# VibeBrain2.net
KiCad netlist of a schematic drawn in EAGLE
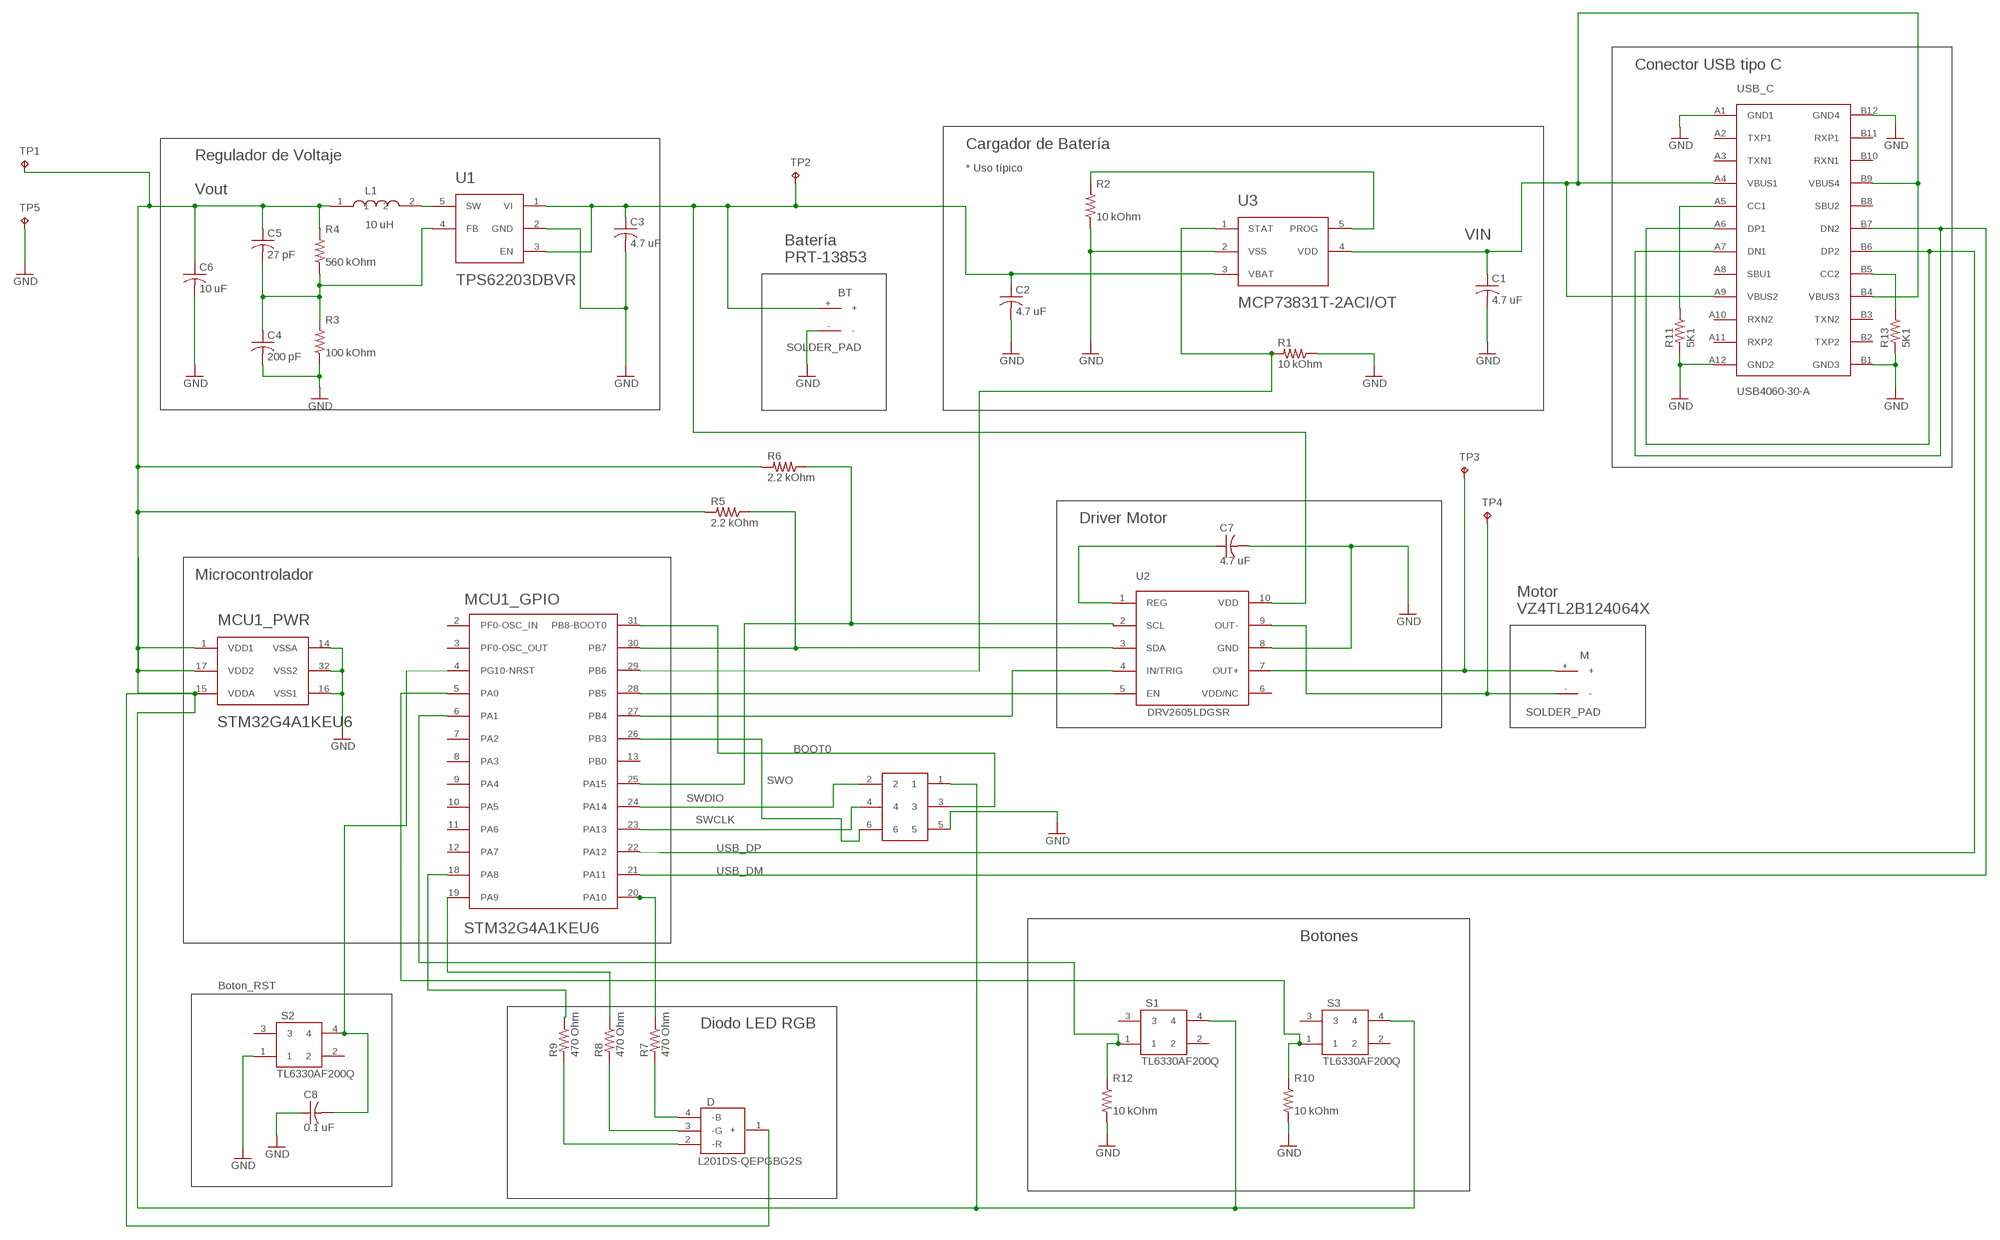
[diagram p0: schematic, sheet 1]

(export (version "E")
  (design (tool "Eeschema 10.0.6"))
  (components
    (comp (ref "BT")
      (value "SOLDER_PAD")
      (footprint "eagle-import:SMD")
      (libsource (lib "eagle-import") (part "PADS"))
    )
    (comp (ref "C1")
      (value "4.7 uF")
      (footprint "eagle-import:C0402")
      (fields (field (name "PARTNO") "GRM155R60J475ME47J"))
      (libsource (lib "eagle-import") (part "C-USC0402"))
    )
    (comp (ref "C2")
      (value "4.7 uF")
      (footprint "eagle-import:C0402")
      (fields (field (name "PARTNO") "GRM155R60J475ME47J"))
      (libsource (lib "eagle-import") (part "C-USC0402"))
    )
    (comp (ref "C3")
      (value "4.7 uF")
      (footprint "eagle-import:C0402")
      (fields (field (name "PARTNO") "GRM155R60J475ME47J"))
      (libsource (lib "eagle-import") (part "C-USC0402"))
    )
    (comp (ref "C4")
      (value "200 pF")
      (footprint "eagle-import:C0402")
      (fields (field (name "PARTNO") "GCM1555C1H201FA16D"))
      (libsource (lib "eagle-import") (part "C-USC0402"))
    )
    (comp (ref "C5")
      (value "27 pF")
      (footprint "eagle-import:C0402")
      (fields (field (name "PARTNO") "GCM1555C1H270JA16D"))
      (libsource (lib "eagle-import") (part "C-USC0402"))
    )
    (comp (ref "C6")
      (value "10 uF")
      (footprint "eagle-import:C0402")
      (fields (field (name "PARTNO") "GRM155R60J106ME05J"))
      (libsource (lib "eagle-import") (part "C-USC0402"))
    )
    (comp (ref "C7")
      (value "4.7 uF")
      (footprint "eagle-import:C0402")
      (fields (field (name "PARTNO") "GRM155R60J475ME47J"))
      (libsource (lib "eagle-import") (part "C-USC0402"))
    )
    (comp (ref "C8")
      (value "0.1 uF")
      (footprint "eagle-import:C0402")
      (fields (field (name "PARTNO") "GCM155R71C104KA55J"))
      (libsource (lib "eagle-import") (part "C-USC0402"))
    )
    (comp (ref "D")
      (value "L201DS-QEPGBG2S")
      (footprint "eagle-import:SMD")
      (libsource (lib "eagle-import") (part "L201DS-QEPGBG2S"))
    )
    (comp (ref "J1")
      (value "TC2030-IDC")
      (footprint "eagle-import:TC2030-IDC-FP")
      (libsource (lib "eagle-import") (part "TC2030-IDC-FP"))
    )
    (comp (ref "L1")
      (value "10 uH")
      (footprint "eagle-import:SMD")
      (fields (field (name "PARTNO") "LQW15DN100M00D"))
      (libsource (lib "eagle-import") (part "LQW15DN100M00D-ME"))
    )
    (comp (ref "M")
      (value "SOLDER_PAD")
      (footprint "eagle-import:SMD")
      (libsource (lib "eagle-import") (part "PADS"))
    )
    (comp (ref "MCU1")
      (value "STM32G4A1KEU6")
      (footprint "eagle-import:32-UFQFPN(5X5)")
      (fields (field (name "PARTNO") "STM32G4A1KEU6 "))
      (libsource (lib "eagle-import") (part "STM32G4A1KEU6"))
    )
    (comp (ref "R1")
      (value "10 kOhm")
      (footprint "eagle-import:R0402")
      (fields (field (name "PARTNO") "RMCF0402FT10K0"))
      (libsource (lib "eagle-import") (part "R-US_R0402"))
    )
    (comp (ref "R2")
      (value "10 kOhm")
      (footprint "eagle-import:R0402")
      (fields (field (name "PARTNO") "RMCF0402FT10K0"))
      (libsource (lib "eagle-import") (part "R-US_R0402"))
    )
    (comp (ref "R3")
      (value "100 kOhm")
      (footprint "eagle-import:R0402")
      (fields (field (name "PARTNO") "RMCF0402FT100K"))
      (libsource (lib "eagle-import") (part "R-US_R0402"))
    )
    (comp (ref "R4")
      (value "560 kOhm")
      (footprint "eagle-import:R0402")
      (fields (field (name "PARTNO") "ERJ-2RKF5603X"))
      (libsource (lib "eagle-import") (part "R-US_R0402"))
    )
    (comp (ref "R5")
      (value "2.2 kOhm")
      (footprint "eagle-import:R0402")
      (fields (field (name "PARTNO") "RMCF0402JT2K20"))
      (libsource (lib "eagle-import") (part "R-US_R0402"))
    )
    (comp (ref "R6")
      (value "2.2 kOhm")
      (footprint "eagle-import:R0402")
      (fields (field (name "PARTNO") "RMCF0402JT2K20"))
      (libsource (lib "eagle-import") (part "R-US_R0402"))
    )
    (comp (ref "R7")
      (value "470 Ohm")
      (footprint "eagle-import:R0402")
      (fields (field (name "PARTNO") "RMCF0402FT470R"))
      (libsource (lib "eagle-import") (part "R-US_R0402"))
    )
    (comp (ref "R8")
      (value "470 Ohm")
      (footprint "eagle-import:R0402")
      (fields (field (name "PARTNO") "RMCF0402FT470R"))
      (libsource (lib "eagle-import") (part "R-US_R0402"))
    )
    (comp (ref "R9")
      (value "470 Ohm")
      (footprint "eagle-import:R0402")
      (fields (field (name "PARTNO") "RMCF0402FT470R"))
      (libsource (lib "eagle-import") (part "R-US_R0402"))
    )
    (comp (ref "R10")
      (value "10 kOhm")
      (footprint "eagle-import:R0402")
      (fields (field (name "PARTNO") "RMCF0402FT10K0"))
      (libsource (lib "eagle-import") (part "R-US_R0402"))
    )
    (comp (ref "R11")
      (value "5K1")
      (footprint "eagle-import:R0402")
      (fields (field (name "PARTNO") "RC0402FR-075K1L"))
      (libsource (lib "eagle-import") (part "R-US_R0402"))
    )
    (comp (ref "R12")
      (value "10 kOhm")
      (footprint "eagle-import:R0402")
      (fields (field (name "PARTNO") "RMCF0402FT10K0"))
      (libsource (lib "eagle-import") (part "R-US_R0402"))
    )
    (comp (ref "R13")
      (value "5K1")
      (footprint "eagle-import:R0402")
      (fields (field (name "PARTNO") "RC0402FR-075K1L"))
      (libsource (lib "eagle-import") (part "R-US_R0402"))
    )
    (comp (ref "S1")
      (value "TL6330AF200Q")
      (footprint "eagle-import:SWITCH")
      (libsource (lib "eagle-import") (part "TL6330AF200Q"))
    )
    (comp (ref "S2")
      (value "TL6330AF200Q")
      (footprint "eagle-import:SWITCH")
      (libsource (lib "eagle-import") (part "TL6330AF200Q"))
    )
    (comp (ref "S3")
      (value "TL6330AF200Q")
      (footprint "eagle-import:SWITCH")
      (libsource (lib "eagle-import") (part "TL6330AF200Q"))
    )
    (comp (ref "TP1")
      (value "TPTP07SQ")
      (footprint "eagle-import:TP07SQ")
      (libsource (lib "eagle-import") (part "TPTP07SQ"))
    )
    (comp (ref "TP2")
      (value "TPTP07SQ")
      (footprint "eagle-import:TP07SQ")
      (libsource (lib "eagle-import") (part "TPTP07SQ"))
    )
    (comp (ref "TP3")
      (value "TPTP07SQ")
      (footprint "eagle-import:TP07SQ")
      (libsource (lib "eagle-import") (part "TPTP07SQ"))
    )
    (comp (ref "TP4")
      (value "TPTP07SQ")
      (footprint "eagle-import:TP07SQ")
      (libsource (lib "eagle-import") (part "TPTP07SQ"))
    )
    (comp (ref "TP5")
      (value "TPTP07SQ")
      (footprint "eagle-import:TP07SQ")
      (libsource (lib "eagle-import") (part "TPTP07SQ"))
    )
    (comp (ref "U1")
      (value "TPS62203DBVR")
      (footprint "eagle-import:SOT-23-5")
      (libsource (lib "eagle-import") (part "TPS62203DBVR"))
    )
    (comp (ref "U2")
      (value "DRV2605LDGSR")
      (footprint "eagle-import:10-VSSOP")
      (libsource (lib "eagle-import") (part "DRV2605LDGSR"))
    )
    (comp (ref "U3")
      (value "MCP73831T-2ACI/OT")
      (footprint "eagle-import:SOT-23-5")
      (libsource (lib "eagle-import") (part "MCP73831T-2ACI-OT"))
    )
    (comp (ref "USB_C")
      (value "USB4060-30-A")
      (footprint "eagle-import:USB_C")
      (libsource (lib "eagle-import") (part "USB4060-30-A"))
    )
  )
  (nets
    (net (code "1") (name "/VDD{slash}NC") (class "Default")
      (node (ref "U2") (pin "6") (pinfunction "VDD/NC_6") (pintype "power_in"))
    )
    (net (code "2") (name "GND") (class "Default")
      (node (ref "BT") (pin "-") (pinfunction "-_-") (pintype "passive"))
      (node (ref "C1") (pin "2") (pinfunction "2_2") (pintype "passive"))
      (node (ref "C2") (pin "2") (pinfunction "2_2") (pintype "passive"))
      (node (ref "C3") (pin "2") (pinfunction "2_2") (pintype "passive"))
      (node (ref "C4") (pin "2") (pinfunction "2_2") (pintype "passive"))
      (node (ref "C6") (pin "2") (pinfunction "2_2") (pintype "passive"))
      (node (ref "C7") (pin "2") (pinfunction "2_2") (pintype "passive"))
      (node (ref "C8") (pin "1") (pinfunction "1_1") (pintype "passive"))
      (node (ref "J1") (pin "5") (pinfunction "5_5") (pintype "passive"))
      (node (ref "MCU1") (pin "14") (pinfunction "VSSA_14") (pintype "passive"))
      (node (ref "MCU1") (pin "16") (pinfunction "VSS1_16") (pintype "passive"))
      (node (ref "MCU1") (pin "32") (pinfunction "VSS2_32") (pintype "passive"))
      (node (ref "R1") (pin "1") (pinfunction "1_1") (pintype "passive"))
      (node (ref "R10") (pin "2") (pinfunction "2_2") (pintype "passive"))
      (node (ref "R11") (pin "2") (pinfunction "2_2") (pintype "passive"))
      (node (ref "R12") (pin "2") (pinfunction "2_2") (pintype "passive"))
      (node (ref "R13") (pin "2") (pinfunction "2_2") (pintype "passive"))
      (node (ref "R2") (pin "1") (pinfunction "1_1") (pintype "passive"))
      (node (ref "R3") (pin "1") (pinfunction "1_1") (pintype "passive"))
      (node (ref "S2") (pin "1") (pinfunction "1_1") (pintype "passive"))
      (node (ref "TP5") (pin "TP") (pinfunction "TP_TP") (pintype "input"))
      (node (ref "U1") (pin "2") (pinfunction "GND_2") (pintype "passive"))
      (node (ref "U2") (pin "8") (pinfunction "GND_8") (pintype "passive"))
      (node (ref "U3") (pin "2") (pinfunction "VSS_2") (pintype "passive"))
      (node (ref "USB_C") (pin "A1") (pinfunction "GND1_A1") (pintype "power_in"))
      (node (ref "USB_C") (pin "A12") (pinfunction "GND2_A12") (pintype "power_in"))
      (node (ref "USB_C") (pin "B1") (pinfunction "GND3_B1") (pintype "power_in"))
      (node (ref "USB_C") (pin "B12") (pinfunction "GND4_B12") (pintype "power_in"))
    )
    (net (code "3") (name "Net-(D-+)") (class "Default")
      (node (ref "C5") (pin "1") (pinfunction "1_1") (pintype "passive"))
      (node (ref "C6") (pin "1") (pinfunction "1_1") (pintype "passive"))
      (node (ref "D") (pin "1") (pinfunction "+_1") (pintype "passive"))
      (node (ref "J1") (pin "1") (pinfunction "1_1") (pintype "passive"))
      (node (ref "L1") (pin "1") (pinfunction "1_1") (pintype "passive"))
      (node (ref "MCU1") (pin "1") (pinfunction "VDD1_1") (pintype "passive"))
      (node (ref "MCU1") (pin "15") (pinfunction "VDDA_15") (pintype "passive"))
      (node (ref "MCU1") (pin "17") (pinfunction "VDD2_17") (pintype "passive"))
      (node (ref "R4") (pin "2") (pinfunction "2_2") (pintype "passive"))
      (node (ref "R5") (pin "2") (pinfunction "2_2") (pintype "passive"))
      (node (ref "R6") (pin "2") (pinfunction "2_2") (pintype "passive"))
      (node (ref "S1") (pin "4") (pinfunction "4_4") (pintype "passive"))
      (node (ref "S3") (pin "4") (pinfunction "4_4") (pintype "passive"))
      (node (ref "TP1") (pin "TP") (pinfunction "TP_TP") (pintype "input"))
    )
    (net (code "4") (name "Net-(D--B)") (class "Default")
      (node (ref "D") (pin "4") (pinfunction "-B_4") (pintype "passive"))
      (node (ref "R7") (pin "2") (pinfunction "2_2") (pintype "passive"))
    )
    (net (code "5") (name "Net-(D--G)") (class "Default")
      (node (ref "D") (pin "3") (pinfunction "-G_3") (pintype "passive"))
      (node (ref "R8") (pin "2") (pinfunction "2_2") (pintype "passive"))
    )
    (net (code "6") (name "Net-(D--R)") (class "Default")
      (node (ref "D") (pin "2") (pinfunction "-R_2") (pintype "passive"))
      (node (ref "R9") (pin "2") (pinfunction "2_2") (pintype "passive"))
    )
    (net (code "7") (name "Net-(MCU1A-PA0)") (class "Default")
      (node (ref "MCU1") (pin "5") (pinfunction "PA0_5") (pintype "bidirectional"))
      (node (ref "R10") (pin "1") (pinfunction "1_1") (pintype "passive"))
      (node (ref "S3") (pin "1") (pinfunction "1_1") (pintype "passive"))
    )
    (net (code "8") (name "Net-(MCU1A-PA1)") (class "Default")
      (node (ref "MCU1") (pin "6") (pinfunction "PA1_6") (pintype "bidirectional"))
      (node (ref "R12") (pin "1") (pinfunction "1_1") (pintype "passive"))
      (node (ref "S1") (pin "1") (pinfunction "1_1") (pintype "passive"))
    )
    (net (code "9") (name "Net-(MCU1A-PA8)") (class "Default")
      (node (ref "MCU1") (pin "18") (pinfunction "PA8_18") (pintype "bidirectional"))
      (node (ref "R9") (pin "1") (pinfunction "1_1") (pintype "passive"))
    )
    (net (code "10") (name "Net-(MCU1A-PA9)") (class "Default")
      (node (ref "MCU1") (pin "19") (pinfunction "PA9_19") (pintype "bidirectional"))
      (node (ref "R8") (pin "1") (pinfunction "1_1") (pintype "passive"))
    )
    (net (code "11") (name "Net-(MCU1A-PA10)") (class "Default")
      (node (ref "MCU1") (pin "20") (pinfunction "PA10_20") (pintype "bidirectional"))
      (node (ref "R7") (pin "1") (pinfunction "1_1") (pintype "passive"))
    )
    (net (code "12") (name "Net-(MCU1A-PA11)") (class "Default")
      (node (ref "MCU1") (pin "21") (pinfunction "PA11_21") (pintype "bidirectional"))
      (node (ref "USB_C") (pin "A7") (pinfunction "DN1_A7") (pintype "bidirectional"))
      (node (ref "USB_C") (pin "B7") (pinfunction "DN2_B7") (pintype "bidirectional"))
    )
    (net (code "13") (name "Net-(MCU1A-PA12)") (class "Default")
      (node (ref "MCU1") (pin "22") (pinfunction "PA12_22") (pintype "bidirectional"))
      (node (ref "USB_C") (pin "A6") (pinfunction "DP1_A6") (pintype "bidirectional"))
      (node (ref "USB_C") (pin "B6") (pinfunction "DP2_B6") (pintype "bidirectional"))
    )
    (net (code "14") (name "Net-(MCU1A-PA13)") (class "Default")
      (node (ref "J1") (pin "4") (pinfunction "4_4") (pintype "passive"))
      (node (ref "MCU1") (pin "23") (pinfunction "PA13_23") (pintype "bidirectional"))
    )
    (net (code "15") (name "Net-(MCU1A-PA14)") (class "Default")
      (node (ref "J1") (pin "2") (pinfunction "2_2") (pintype "passive"))
      (node (ref "MCU1") (pin "24") (pinfunction "PA14_24") (pintype "bidirectional"))
    )
    (net (code "16") (name "Net-(MCU1A-PA15)") (class "Default")
      (node (ref "MCU1") (pin "25") (pinfunction "PA15_25") (pintype "bidirectional"))
      (node (ref "R6") (pin "1") (pinfunction "1_1") (pintype "passive"))
      (node (ref "U2") (pin "2") (pinfunction "SCL_2") (pintype "input"))
    )
    (net (code "17") (name "Net-(MCU1A-PB3)") (class "Default")
      (node (ref "J1") (pin "6") (pinfunction "6_6") (pintype "passive"))
      (node (ref "MCU1") (pin "26") (pinfunction "PB3_26") (pintype "bidirectional"))
    )
    (net (code "18") (name "Net-(MCU1A-PB4)") (class "Default")
      (node (ref "MCU1") (pin "27") (pinfunction "PB4_27") (pintype "bidirectional"))
      (node (ref "U2") (pin "4") (pinfunction "IN/TRIG_4") (pintype "input"))
    )
    (net (code "19") (name "Net-(MCU1A-PB5)") (class "Default")
      (node (ref "MCU1") (pin "28") (pinfunction "PB5_28") (pintype "bidirectional"))
      (node (ref "U2") (pin "5") (pinfunction "EN_5") (pintype "input"))
    )
    (net (code "20") (name "Net-(MCU1A-PB6)") (class "Default")
      (node (ref "MCU1") (pin "29") (pinfunction "PB6_29") (pintype "bidirectional"))
      (node (ref "R1") (pin "2") (pinfunction "2_2") (pintype "passive"))
      (node (ref "U3") (pin "1") (pinfunction "STAT_1") (pintype "output"))
    )
    (net (code "21") (name "Net-(MCU1A-PB7)") (class "Default")
      (node (ref "MCU1") (pin "30") (pinfunction "PB7_30") (pintype "bidirectional"))
      (node (ref "R5") (pin "1") (pinfunction "1_1") (pintype "passive"))
      (node (ref "U2") (pin "3") (pinfunction "SDA_3") (pintype "bidirectional"))
    )
    (net (code "22") (name "Net-(MCU1A-PB8-BOOT0)") (class "Default")
      (node (ref "J1") (pin "3") (pinfunction "3_3") (pintype "passive"))
      (node (ref "MCU1") (pin "31") (pinfunction "PB8-BOOT0_31") (pintype "bidirectional"))
    )
    (net (code "23") (name "Net-(MCU1A-PG10-NRST)") (class "Default")
      (node (ref "C8") (pin "2") (pinfunction "2_2") (pintype "passive"))
      (node (ref "MCU1") (pin "4") (pinfunction "PG10-NRST_4") (pintype "bidirectional"))
      (node (ref "S2") (pin "4") (pinfunction "4_4") (pintype "passive"))
    )
    (net (code "24") (name "Net-(U1-EN)") (class "Default")
      (node (ref "BT") (pin "+") (pinfunction "+_+") (pintype "passive"))
      (node (ref "C2") (pin "1") (pinfunction "1_1") (pintype "passive"))
      (node (ref "C3") (pin "1") (pinfunction "1_1") (pintype "passive"))
      (node (ref "TP2") (pin "TP") (pinfunction "TP_TP") (pintype "input"))
      (node (ref "U1") (pin "1") (pinfunction "VI_1") (pintype "passive"))
      (node (ref "U1") (pin "3") (pinfunction "EN_3") (pintype "passive"))
      (node (ref "U2") (pin "10") (pinfunction "VDD_10") (pintype "power_in"))
      (node (ref "U3") (pin "3") (pinfunction "VBAT_3") (pintype "passive"))
    )
    (net (code "25") (name "Net-(U1-FB)") (class "Default")
      (node (ref "C4") (pin "1") (pinfunction "1_1") (pintype "passive"))
      (node (ref "C5") (pin "2") (pinfunction "2_2") (pintype "passive"))
      (node (ref "R3") (pin "2") (pinfunction "2_2") (pintype "passive"))
      (node (ref "R4") (pin "1") (pinfunction "1_1") (pintype "passive"))
      (node (ref "U1") (pin "4") (pinfunction "FB_4") (pintype "passive"))
    )
    (net (code "26") (name "Net-(U1-SW)") (class "Default")
      (node (ref "L1") (pin "2") (pinfunction "2_2") (pintype "passive"))
      (node (ref "U1") (pin "5") (pinfunction "SW_5") (pintype "passive"))
    )
    (net (code "27") (name "Net-(U2-OUT+)") (class "Default")
      (node (ref "M") (pin "+") (pinfunction "+_+") (pintype "passive"))
      (node (ref "TP3") (pin "TP") (pinfunction "TP_TP") (pintype "input"))
      (node (ref "U2") (pin "7") (pinfunction "OUT+_7") (pintype "output"))
    )
    (net (code "28") (name "Net-(U2-OUT-)") (class "Default")
      (node (ref "M") (pin "-") (pinfunction "-_-") (pintype "passive"))
      (node (ref "TP4") (pin "TP") (pinfunction "TP_TP") (pintype "input"))
      (node (ref "U2") (pin "9") (pinfunction "OUT-_9") (pintype "output"))
    )
    (net (code "29") (name "Net-(U2-REG)") (class "Default")
      (node (ref "C7") (pin "1") (pinfunction "1_1") (pintype "passive"))
      (node (ref "U2") (pin "1") (pinfunction "REG_1") (pintype "output"))
    )
    (net (code "30") (name "Net-(U3-PROG)") (class "Default")
      (node (ref "R2") (pin "2") (pinfunction "2_2") (pintype "passive"))
      (node (ref "U3") (pin "5") (pinfunction "PROG_5") (pintype "passive"))
    )
    (net (code "31") (name "Net-(U3-VDD)") (class "Default")
      (node (ref "C1") (pin "1") (pinfunction "1_1") (pintype "passive"))
      (node (ref "U3") (pin "4") (pinfunction "VDD_4") (pintype "passive"))
      (node (ref "USB_C") (pin "A4") (pinfunction "VBUS1_A4") (pintype "passive"))
      (node (ref "USB_C") (pin "A9") (pinfunction "VBUS2_A9") (pintype "passive"))
      (node (ref "USB_C") (pin "B4") (pinfunction "VBUS3_B4") (pintype "passive"))
      (node (ref "USB_C") (pin "B9") (pinfunction "VBUS4_B9") (pintype "passive"))
    )
    (net (code "32") (name "Net-(USB_C-CC1)") (class "Default")
      (node (ref "R11") (pin "1") (pinfunction "1_1") (pintype "passive"))
      (node (ref "USB_C") (pin "A5") (pinfunction "CC1_A5") (pintype "passive"))
    )
    (net (code "33") (name "Net-(USB_C-CC2)") (class "Default")
      (node (ref "R13") (pin "1") (pinfunction "1_1") (pintype "passive"))
      (node (ref "USB_C") (pin "B5") (pinfunction "CC2_B5") (pintype "passive"))
    )
    (net (code "34") (name "unconnected-(MCU1A-PA2-Pad7)") (class "Default")
      (node (ref "MCU1") (pin "7") (pinfunction "PA2_7") (pintype "bidirectional"))
    )
    (net (code "35") (name "unconnected-(MCU1A-PA3-Pad8)") (class "Default")
      (node (ref "MCU1") (pin "8") (pinfunction "PA3_8") (pintype "bidirectional"))
    )
    (net (code "36") (name "unconnected-(MCU1A-PA4-Pad9)") (class "Default")
      (node (ref "MCU1") (pin "9") (pinfunction "PA4_9") (pintype "bidirectional"))
    )
    (net (code "37") (name "unconnected-(MCU1A-PA5-Pad10)") (class "Default")
      (node (ref "MCU1") (pin "10") (pinfunction "PA5_10") (pintype "bidirectional"))
    )
    (net (code "38") (name "unconnected-(MCU1A-PA6-Pad11)") (class "Default")
      (node (ref "MCU1") (pin "11") (pinfunction "PA6_11") (pintype "bidirectional"))
    )
    (net (code "39") (name "unconnected-(MCU1A-PA7-Pad12)") (class "Default")
      (node (ref "MCU1") (pin "12") (pinfunction "PA7_12") (pintype "bidirectional"))
    )
    (net (code "40") (name "unconnected-(MCU1A-PB0-Pad13)") (class "Default")
      (node (ref "MCU1") (pin "13") (pinfunction "PB0_13") (pintype "bidirectional"))
    )
    (net (code "41") (name "unconnected-(MCU1A-PF0-OSC_IN-Pad2)") (class "Default")
      (node (ref "MCU1") (pin "2") (pinfunction "PF0-OSC_IN_2") (pintype "bidirectional"))
    )
    (net (code "42") (name "unconnected-(MCU1A-PF0-OSC_OUT-Pad3)") (class "Default")
      (node (ref "MCU1") (pin "3") (pinfunction "PF0-OSC_OUT_3") (pintype "bidirectional"))
    )
    (net (code "43") (name "unconnected-(S1-Pad2)") (class "Default")
      (node (ref "S1") (pin "2") (pinfunction "2_2") (pintype "passive"))
    )
    (net (code "44") (name "unconnected-(S1-Pad3)") (class "Default")
      (node (ref "S1") (pin "3") (pinfunction "3_3") (pintype "passive"))
    )
    (net (code "45") (name "unconnected-(S2-Pad2)") (class "Default")
      (node (ref "S2") (pin "2") (pinfunction "2_2") (pintype "passive"))
    )
    (net (code "46") (name "unconnected-(S2-Pad3)") (class "Default")
      (node (ref "S2") (pin "3") (pinfunction "3_3") (pintype "passive"))
    )
    (net (code "47") (name "unconnected-(S3-Pad2)") (class "Default")
      (node (ref "S3") (pin "2") (pinfunction "2_2") (pintype "passive"))
    )
    (net (code "48") (name "unconnected-(S3-Pad3)") (class "Default")
      (node (ref "S3") (pin "3") (pinfunction "3_3") (pintype "passive"))
    )
    (net (code "49") (name "unconnected-(USB_C-RXN1-PadB10)") (class "Default")
      (node (ref "USB_C") (pin "B10") (pinfunction "RXN1_B10") (pintype "bidirectional"))
    )
    (net (code "50") (name "unconnected-(USB_C-RXN2-PadA10)") (class "Default")
      (node (ref "USB_C") (pin "A10") (pinfunction "RXN2_A10") (pintype "bidirectional"))
    )
    (net (code "51") (name "unconnected-(USB_C-RXP1-PadB11)") (class "Default")
      (node (ref "USB_C") (pin "B11") (pinfunction "RXP1_B11") (pintype "bidirectional"))
    )
    (net (code "52") (name "unconnected-(USB_C-RXP2-PadA11)") (class "Default")
      (node (ref "USB_C") (pin "A11") (pinfunction "RXP2_A11") (pintype "bidirectional"))
    )
    (net (code "53") (name "unconnected-(USB_C-SBU1-PadA8)") (class "Default")
      (node (ref "USB_C") (pin "A8") (pinfunction "SBU1_A8") (pintype "bidirectional"))
    )
    (net (code "54") (name "unconnected-(USB_C-SBU2-PadB8)") (class "Default")
      (node (ref "USB_C") (pin "B8") (pinfunction "SBU2_B8") (pintype "bidirectional"))
    )
    (net (code "55") (name "unconnected-(USB_C-TXN1-PadA3)") (class "Default")
      (node (ref "USB_C") (pin "A3") (pinfunction "TXN1_A3") (pintype "bidirectional"))
    )
    (net (code "56") (name "unconnected-(USB_C-TXN2-PadB3)") (class "Default")
      (node (ref "USB_C") (pin "B3") (pinfunction "TXN2_B3") (pintype "bidirectional"))
    )
    (net (code "57") (name "unconnected-(USB_C-TXP1-PadA2)") (class "Default")
      (node (ref "USB_C") (pin "A2") (pinfunction "TXP1_A2") (pintype "bidirectional"))
    )
    (net (code "58") (name "unconnected-(USB_C-TXP2-PadB2)") (class "Default")
      (node (ref "USB_C") (pin "B2") (pinfunction "TXP2_B2") (pintype "bidirectional"))
    )
  )
)
